# 01_detection_counter.net
KiCad netlist of a schematic drawn in Altium Designer
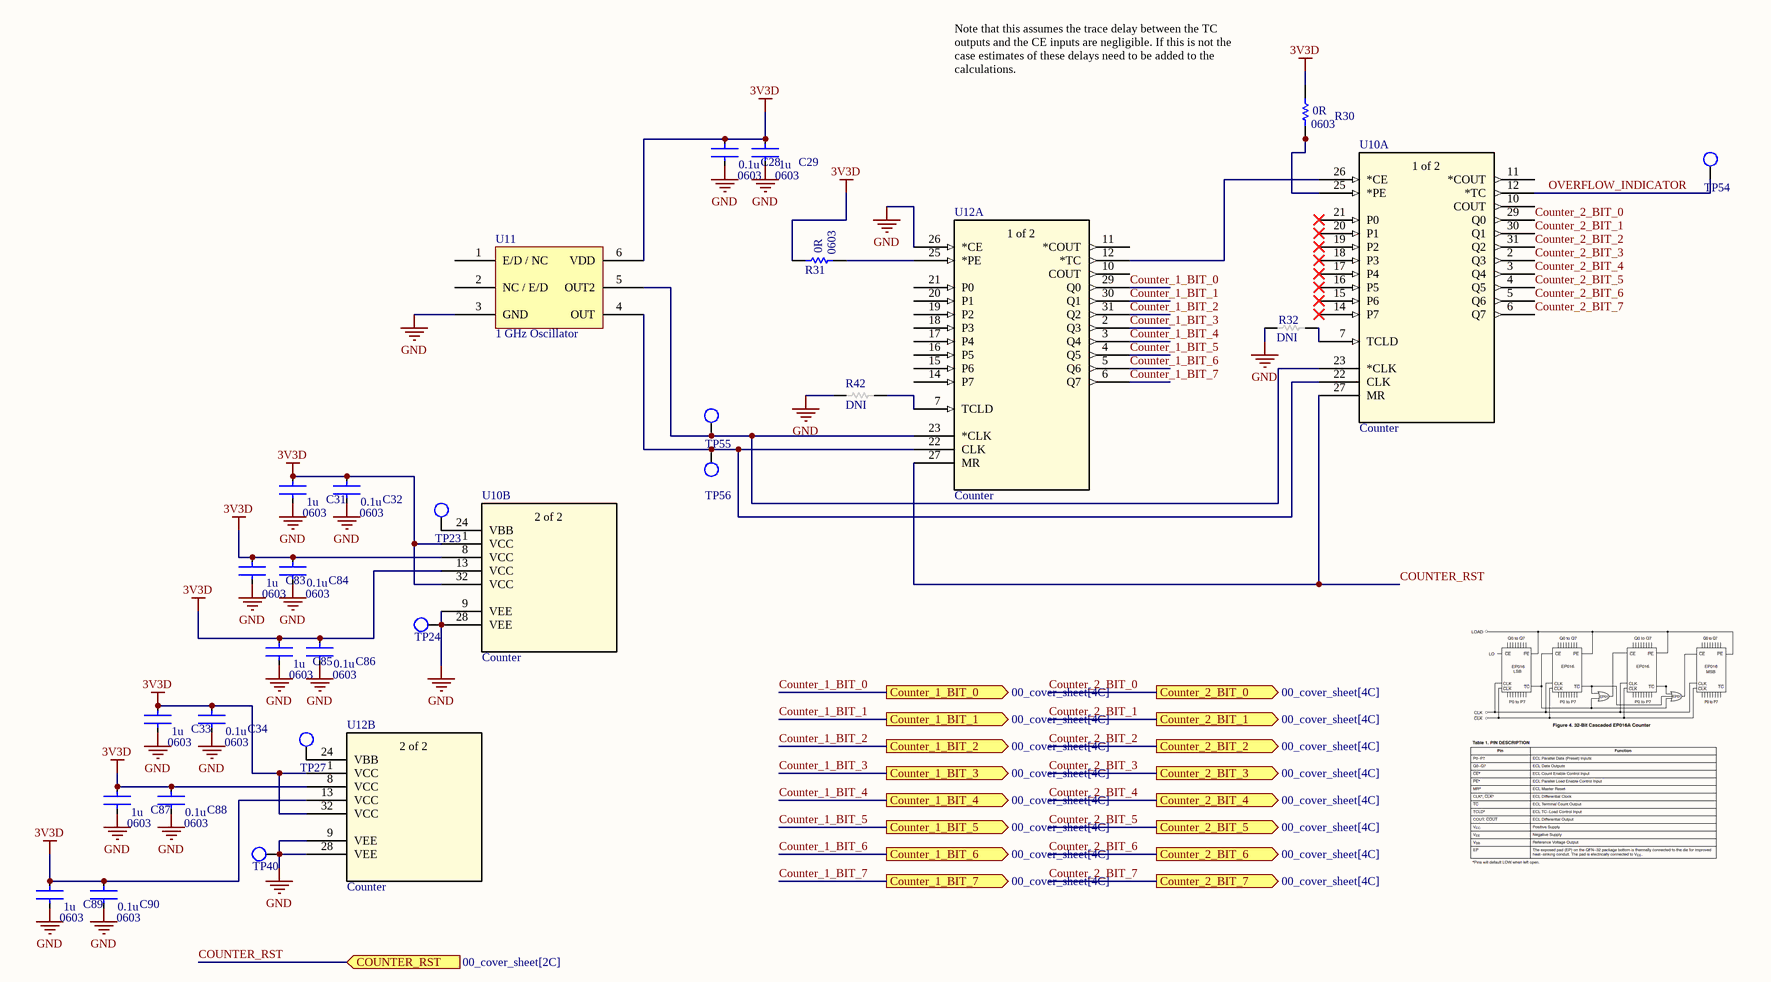
[diagram p0: 01_detection_counter.SchDoc]

(export (version "E")
  (design (tool "Eeschema 10.0.6"))
  (components
    (comp (ref "C28")
      (value "CGA3E2X7R1H104K080AA")
      (footprint "CAPTDK0603")
      (description "CAP CER 0.1UF 50V X7R 0603")
      (libsource (lib "tcspc00") (part "CGA3E2X7R1H104K080AA"))
    )
    (comp (ref "C29")
      (value "C1608X5R1E105K080AC")
      (footprint "CAPTDK0603")
      (description "CAP CER 1UF 25V X5R 0603")
      (libsource (lib "tcspc00") (part "C1608X5R1E105K080AC"))
    )
    (comp (ref "C31")
      (value "C1608X5R1E105K080AC")
      (footprint "CAPTDK0603")
      (description "CAP CER 1UF 25V X5R 0603")
      (libsource (lib "tcspc00") (part "C1608X5R1E105K080AC"))
    )
    (comp (ref "C32")
      (value "CGA3E2X7R1H104K080AA")
      (footprint "CAPTDK0603")
      (description "CAP CER 0.1UF 50V X7R 0603")
      (libsource (lib "tcspc00") (part "CGA3E2X7R1H104K080AA"))
    )
    (comp (ref "C33")
      (value "C1608X5R1E105K080AC")
      (footprint "CAPTDK0603")
      (description "CAP CER 1UF 25V X5R 0603")
      (libsource (lib "tcspc00") (part "C1608X5R1E105K080AC"))
    )
    (comp (ref "C34")
      (value "CGA3E2X7R1H104K080AA")
      (footprint "CAPTDK0603")
      (description "CAP CER 0.1UF 50V X7R 0603")
      (libsource (lib "tcspc00") (part "CGA3E2X7R1H104K080AA"))
    )
    (comp (ref "C83")
      (value "C1608X5R1E105K080AC")
      (footprint "CAPTDK0603")
      (description "CAP CER 1UF 25V X5R 0603")
      (libsource (lib "tcspc00") (part "C1608X5R1E105K080AC"))
    )
    (comp (ref "C84")
      (value "CGA3E2X7R1H104K080AA")
      (footprint "CAPTDK0603")
      (description "CAP CER 0.1UF 50V X7R 0603")
      (libsource (lib "tcspc00") (part "CGA3E2X7R1H104K080AA"))
    )
    (comp (ref "C85")
      (value "C1608X5R1E105K080AC")
      (footprint "CAPTDK0603")
      (description "CAP CER 1UF 25V X5R 0603")
      (libsource (lib "tcspc00") (part "C1608X5R1E105K080AC"))
    )
    (comp (ref "C86")
      (value "CGA3E2X7R1H104K080AA")
      (footprint "CAPTDK0603")
      (description "CAP CER 0.1UF 50V X7R 0603")
      (libsource (lib "tcspc00") (part "CGA3E2X7R1H104K080AA"))
    )
    (comp (ref "C87")
      (value "C1608X5R1E105K080AC")
      (footprint "CAPTDK0603")
      (description "CAP CER 1UF 25V X5R 0603")
      (libsource (lib "tcspc00") (part "C1608X5R1E105K080AC"))
    )
    (comp (ref "C88")
      (value "CGA3E2X7R1H104K080AA")
      (footprint "CAPTDK0603")
      (description "CAP CER 0.1UF 50V X7R 0603")
      (libsource (lib "tcspc00") (part "CGA3E2X7R1H104K080AA"))
    )
    (comp (ref "C89")
      (value "C1608X5R1E105K080AC")
      (footprint "CAPTDK0603")
      (description "CAP CER 1UF 25V X5R 0603")
      (libsource (lib "tcspc00") (part "C1608X5R1E105K080AC"))
    )
    (comp (ref "C90")
      (value "CGA3E2X7R1H104K080AA")
      (footprint "CAPTDK0603")
      (description "CAP CER 0.1UF 50V X7R 0603")
      (libsource (lib "tcspc00") (part "CGA3E2X7R1H104K080AA"))
    )
    (comp (ref "R30")
      (value "RMCF0603ZT0R00")
      (footprint "RES-STACK-POLE-0603")
      (description "RES 0 OHM JUMPER 1/10W 0603")
      (libsource (lib "tcspc00") (part "RMCF0603ZT0R00"))
    )
    (comp (ref "R31")
      (value "RMCF0603ZT0R00")
      (footprint "RES-STACK-POLE-0603")
      (description "RES 0 OHM JUMPER 1/10W 0603")
      (libsource (lib "tcspc00") (part "RMCF0603ZT0R00"))
    )
    (comp (ref "R32")
      (value "DNI")
      (footprint "RES_0603")
      (description "RES DNI 0603")
      (libsource (lib "tcspc00") (part "R0603"))
    )
    (comp (ref "R42")
      (value "DNI")
      (footprint "RES_0603")
      (description "RES DNI 0603")
      (libsource (lib "tcspc00") (part "R0603"))
    )
    (comp (ref "TP23")
      (value "TESTPOINT_S")
      (footprint "TESTPOINT_S")
      (description "Testpoint Surface Pad")
      (libsource (lib "tcspc00") (part "TESTPOINT_S"))
    )
    (comp (ref "TP24")
      (value "TESTPOINT_S")
      (footprint "TESTPOINT_S")
      (description "Testpoint Surface Pad")
      (libsource (lib "tcspc00") (part "TESTPOINT_S"))
    )
    (comp (ref "TP27")
      (value "TESTPOINT_S")
      (footprint "TESTPOINT_S")
      (description "Testpoint Surface Pad")
      (libsource (lib "tcspc00") (part "TESTPOINT_S"))
    )
    (comp (ref "TP40")
      (value "TESTPOINT_S")
      (footprint "TESTPOINT_S")
      (description "Testpoint Surface Pad")
      (libsource (lib "tcspc00") (part "TESTPOINT_S"))
    )
    (comp (ref "TP54")
      (value "TESTPOINT_S")
      (footprint "TESTPOINT_S")
      (description "Testpoint Surface Pad")
      (libsource (lib "tcspc00") (part "TESTPOINT_S"))
    )
    (comp (ref "TP55")
      (value "TESTPOINT_S")
      (footprint "TESTPOINT_S")
      (description "Testpoint Surface Pad")
      (libsource (lib "tcspc00") (part "TESTPOINT_S"))
    )
    (comp (ref "TP56")
      (value "TESTPOINT_S")
      (footprint "TESTPOINT_S")
      (description "Testpoint Surface Pad")
      (libsource (lib "tcspc00") (part "TESTPOINT_S"))
    )
    (comp (ref "U10")
      (value "Counter")
      (footprint "LQFP32_7X7_ONS")
      (description "IC BINARY COUNTER 8-BIT 32LQFP")
      (libsource (lib "tcspc00") (part "MC100EP016AFAG"))
    )
    (comp (ref "U11")
      (value "1 GHz Oscillator")
      (footprint "XLP736A00.0000001")
      (fields (field (name "MANUFACTURER") "Renesas Electronics Corporation"))
      (libsource (lib "tcspc00") (part "XLP736A00.000000I"))
    )
    (comp (ref "U12")
      (value "Counter")
      (footprint "LQFP32_7X7_ONS")
      (description "IC BINARY COUNTER 8-BIT 32LQFP")
      (libsource (lib "tcspc00") (part "MC100EP016AFAG"))
    )
  )
  (nets
    (net (code "1") (name "/COUNTER_RST") (class "Default")
      (node (ref "U10") (pin "27") (pinfunction "MR_27") (pintype "passive"))
      (node (ref "U12") (pin "27") (pinfunction "MR_27") (pintype "passive"))
    )
    (net (code "2") (name "/Counter_1_BIT_0") (class "Default")
      (node (ref "U12") (pin "29") (pinfunction "Q0_29") (pintype "output"))
    )
    (net (code "3") (name "/Counter_1_BIT_1") (class "Default")
      (node (ref "U12") (pin "30") (pinfunction "Q1_30") (pintype "output"))
    )
    (net (code "4") (name "/Counter_1_BIT_2") (class "Default")
      (node (ref "U12") (pin "31") (pinfunction "Q2_31") (pintype "output"))
    )
    (net (code "5") (name "/Counter_1_BIT_3") (class "Default")
      (node (ref "U12") (pin "2") (pinfunction "Q3_2") (pintype "output"))
    )
    (net (code "6") (name "/Counter_1_BIT_4") (class "Default")
      (node (ref "U12") (pin "3") (pinfunction "Q4_3") (pintype "output"))
    )
    (net (code "7") (name "/Counter_1_BIT_5") (class "Default")
      (node (ref "U12") (pin "4") (pinfunction "Q5_4") (pintype "output"))
    )
    (net (code "8") (name "/Counter_1_BIT_6") (class "Default")
      (node (ref "U12") (pin "5") (pinfunction "Q6_5") (pintype "output"))
    )
    (net (code "9") (name "/Counter_1_BIT_7") (class "Default")
      (node (ref "U12") (pin "6") (pinfunction "Q7_6") (pintype "output"))
    )
    (net (code "10") (name "/Counter_2_BIT_0") (class "Default")
      (node (ref "U10") (pin "29") (pinfunction "Q0_29") (pintype "output"))
    )
    (net (code "11") (name "/Counter_2_BIT_1") (class "Default")
      (node (ref "U10") (pin "30") (pinfunction "Q1_30") (pintype "output"))
    )
    (net (code "12") (name "/Counter_2_BIT_2") (class "Default")
      (node (ref "U10") (pin "31") (pinfunction "Q2_31") (pintype "output"))
    )
    (net (code "13") (name "/Counter_2_BIT_3") (class "Default")
      (node (ref "U10") (pin "2") (pinfunction "Q3_2") (pintype "output"))
    )
    (net (code "14") (name "/Counter_2_BIT_4") (class "Default")
      (node (ref "U10") (pin "3") (pinfunction "Q4_3") (pintype "output"))
    )
    (net (code "15") (name "/Counter_2_BIT_5") (class "Default")
      (node (ref "U10") (pin "4") (pinfunction "Q5_4") (pintype "output"))
    )
    (net (code "16") (name "/Counter_2_BIT_6") (class "Default")
      (node (ref "U10") (pin "5") (pinfunction "Q6_5") (pintype "output"))
    )
    (net (code "17") (name "/Counter_2_BIT_7") (class "Default")
      (node (ref "U10") (pin "6") (pinfunction "Q7_6") (pintype "output"))
    )
    (net (code "18") (name "/OVERFLOW_INDICATOR") (class "Default")
      (node (ref "TP54") (pin "1") (pinfunction "1_1") (pintype "passive"))
      (node (ref "U10") (pin "12") (pinfunction "*TC_12") (pintype "output"))
    )
    (net (code "19") (name "3V3D") (class "Default")
      (node (ref "C28") (pin "1") (pinfunction "1_1") (pintype "passive"))
      (node (ref "C29") (pin "1") (pinfunction "1_1") (pintype "passive"))
      (node (ref "C31") (pin "1") (pinfunction "1_1") (pintype "passive"))
      (node (ref "C32") (pin "1") (pinfunction "1_1") (pintype "passive"))
      (node (ref "C33") (pin "1") (pinfunction "1_1") (pintype "passive"))
      (node (ref "C34") (pin "1") (pinfunction "1_1") (pintype "passive"))
      (node (ref "C83") (pin "1") (pinfunction "1_1") (pintype "passive"))
      (node (ref "C84") (pin "1") (pinfunction "1_1") (pintype "passive"))
      (node (ref "C85") (pin "1") (pinfunction "1_1") (pintype "passive"))
      (node (ref "C86") (pin "1") (pinfunction "1_1") (pintype "passive"))
      (node (ref "C87") (pin "1") (pinfunction "1_1") (pintype "passive"))
      (node (ref "C88") (pin "1") (pinfunction "1_1") (pintype "passive"))
      (node (ref "C89") (pin "1") (pinfunction "1_1") (pintype "passive"))
      (node (ref "C90") (pin "1") (pinfunction "1_1") (pintype "passive"))
      (node (ref "R30") (pin "2") (pinfunction "2_2") (pintype "passive"))
      (node (ref "R31") (pin "2") (pinfunction "2_2") (pintype "passive"))
      (node (ref "U10") (pin "1") (pinfunction "VCC_1") (pintype "power_in"))
      (node (ref "U10") (pin "13") (pinfunction "VCC_13") (pintype "power_in"))
      (node (ref "U10") (pin "32") (pinfunction "VCC_32") (pintype "power_in"))
      (node (ref "U10") (pin "8") (pinfunction "VCC_8") (pintype "power_in"))
      (node (ref "U11") (pin "6") (pinfunction "VDD_6") (pintype "passive"))
      (node (ref "U12") (pin "1") (pinfunction "VCC_1") (pintype "power_in"))
      (node (ref "U12") (pin "13") (pinfunction "VCC_13") (pintype "power_in"))
      (node (ref "U12") (pin "32") (pinfunction "VCC_32") (pintype "power_in"))
      (node (ref "U12") (pin "8") (pinfunction "VCC_8") (pintype "power_in"))
    )
    (net (code "20") (name "GND") (class "Default")
      (node (ref "C28") (pin "2") (pinfunction "2_2") (pintype "passive"))
      (node (ref "C29") (pin "2") (pinfunction "2_2") (pintype "passive"))
      (node (ref "C31") (pin "2") (pinfunction "2_2") (pintype "passive"))
      (node (ref "C32") (pin "2") (pinfunction "2_2") (pintype "passive"))
      (node (ref "C33") (pin "2") (pinfunction "2_2") (pintype "passive"))
      (node (ref "C34") (pin "2") (pinfunction "2_2") (pintype "passive"))
      (node (ref "C83") (pin "2") (pinfunction "2_2") (pintype "passive"))
      (node (ref "C84") (pin "2") (pinfunction "2_2") (pintype "passive"))
      (node (ref "C85") (pin "2") (pinfunction "2_2") (pintype "passive"))
      (node (ref "C86") (pin "2") (pinfunction "2_2") (pintype "passive"))
      (node (ref "C87") (pin "2") (pinfunction "2_2") (pintype "passive"))
      (node (ref "C88") (pin "2") (pinfunction "2_2") (pintype "passive"))
      (node (ref "C89") (pin "2") (pinfunction "2_2") (pintype "passive"))
      (node (ref "C90") (pin "2") (pinfunction "2_2") (pintype "passive"))
      (node (ref "R32") (pin "1") (pinfunction "1_1") (pintype "passive"))
      (node (ref "R42") (pin "1") (pinfunction "1_1") (pintype "passive"))
      (node (ref "TP24") (pin "1") (pinfunction "1_1") (pintype "passive"))
      (node (ref "TP40") (pin "1") (pinfunction "1_1") (pintype "passive"))
      (node (ref "U10") (pin "28") (pinfunction "VEE_28") (pintype "power_in"))
      (node (ref "U10") (pin "9") (pinfunction "VEE_9") (pintype "power_in"))
      (node (ref "U11") (pin "3") (pinfunction "GND_3") (pintype "passive"))
      (node (ref "U12") (pin "26") (pinfunction "*CE_26") (pintype "input"))
      (node (ref "U12") (pin "28") (pinfunction "VEE_28") (pintype "power_in"))
      (node (ref "U12") (pin "9") (pinfunction "VEE_9") (pintype "power_in"))
    )
    (net (code "21") (name "Net-(U10A-*CE)") (class "Default")
      (node (ref "U10") (pin "26") (pinfunction "*CE_26") (pintype "input"))
      (node (ref "U12") (pin "12") (pinfunction "*TC_12") (pintype "output"))
    )
    (net (code "22") (name "Net-(U10A-*CLK)") (class "Default")
      (node (ref "TP55") (pin "1") (pinfunction "1_1") (pintype "passive"))
      (node (ref "U10") (pin "23") (pinfunction "*CLK_23") (pintype "passive"))
      (node (ref "U11") (pin "5") (pinfunction "OUT2_5") (pintype "passive"))
      (node (ref "U12") (pin "23") (pinfunction "*CLK_23") (pintype "passive"))
    )
    (net (code "23") (name "Net-(U10A-*PE)") (class "Default")
      (node (ref "R30") (pin "1") (pinfunction "1_1") (pintype "passive"))
      (node (ref "U10") (pin "25") (pinfunction "*PE_25") (pintype "input"))
    )
    (net (code "24") (name "Net-(U10A-CLK)") (class "Default")
      (node (ref "TP56") (pin "1") (pinfunction "1_1") (pintype "passive"))
      (node (ref "U10") (pin "22") (pinfunction "CLK_22") (pintype "passive"))
      (node (ref "U11") (pin "4") (pinfunction "OUT_4") (pintype "passive"))
      (node (ref "U12") (pin "22") (pinfunction "CLK_22") (pintype "passive"))
    )
    (net (code "25") (name "Net-(U10A-TCLD)") (class "Default")
      (node (ref "R32") (pin "2") (pinfunction "2_2") (pintype "passive"))
      (node (ref "U10") (pin "7") (pinfunction "TCLD_7") (pintype "input"))
    )
    (net (code "26") (name "Net-(U10B-VBB)") (class "Default")
      (node (ref "TP23") (pin "1") (pinfunction "1_1") (pintype "passive"))
      (node (ref "U10") (pin "24") (pinfunction "VBB_24") (pintype "power_in"))
    )
    (net (code "27") (name "Net-(U12A-*PE)") (class "Default")
      (node (ref "R31") (pin "1") (pinfunction "1_1") (pintype "passive"))
      (node (ref "U12") (pin "25") (pinfunction "*PE_25") (pintype "input"))
    )
    (net (code "28") (name "Net-(U12A-TCLD)") (class "Default")
      (node (ref "R42") (pin "2") (pinfunction "2_2") (pintype "passive"))
      (node (ref "U12") (pin "7") (pinfunction "TCLD_7") (pintype "input"))
    )
    (net (code "29") (name "Net-(U12B-VBB)") (class "Default")
      (node (ref "TP27") (pin "1") (pinfunction "1_1") (pintype "passive"))
      (node (ref "U12") (pin "24") (pinfunction "VBB_24") (pintype "power_in"))
    )
    (net (code "30") (name "unconnected-(U10A-*COUT-Pad11)") (class "Default")
      (node (ref "U10") (pin "11") (pinfunction "*COUT_11") (pintype "output"))
    )
    (net (code "31") (name "unconnected-(U10A-COUT-Pad10)") (class "Default")
      (node (ref "U10") (pin "10") (pinfunction "COUT_10") (pintype "output"))
    )
    (net (code "32") (name "unconnected-(U10A-P0-Pad21)") (class "Default")
      (node (ref "U10") (pin "21") (pinfunction "P0_21") (pintype "input+no_connect"))
    )
    (net (code "33") (name "unconnected-(U10A-P1-Pad20)") (class "Default")
      (node (ref "U10") (pin "20") (pinfunction "P1_20") (pintype "input+no_connect"))
    )
    (net (code "34") (name "unconnected-(U10A-P2-Pad19)") (class "Default")
      (node (ref "U10") (pin "19") (pinfunction "P2_19") (pintype "input+no_connect"))
    )
    (net (code "35") (name "unconnected-(U10A-P3-Pad18)") (class "Default")
      (node (ref "U10") (pin "18") (pinfunction "P3_18") (pintype "input+no_connect"))
    )
    (net (code "36") (name "unconnected-(U10A-P4-Pad17)") (class "Default")
      (node (ref "U10") (pin "17") (pinfunction "P4_17") (pintype "input+no_connect"))
    )
    (net (code "37") (name "unconnected-(U10A-P5-Pad16)") (class "Default")
      (node (ref "U10") (pin "16") (pinfunction "P5_16") (pintype "input+no_connect"))
    )
    (net (code "38") (name "unconnected-(U10A-P6-Pad15)") (class "Default")
      (node (ref "U10") (pin "15") (pinfunction "P6_15") (pintype "input+no_connect"))
    )
    (net (code "39") (name "unconnected-(U10A-P7-Pad14)") (class "Default")
      (node (ref "U10") (pin "14") (pinfunction "P7_14") (pintype "input+no_connect"))
    )
    (net (code "40") (name "unconnected-(U11-E{slash}D_{slash}_NC-Pad1)") (class "Default")
      (node (ref "U11") (pin "1") (pinfunction "E/D_/_NC_1") (pintype "passive"))
    )
    (net (code "41") (name "unconnected-(U11-NC_{slash}_E{slash}D-Pad2)") (class "Default")
      (node (ref "U11") (pin "2") (pinfunction "NC_/_E/D_2") (pintype "passive"))
    )
    (net (code "42") (name "unconnected-(U12A-*COUT-Pad11)") (class "Default")
      (node (ref "U12") (pin "11") (pinfunction "*COUT_11") (pintype "output"))
    )
    (net (code "43") (name "unconnected-(U12A-COUT-Pad10)") (class "Default")
      (node (ref "U12") (pin "10") (pinfunction "COUT_10") (pintype "output"))
    )
    (net (code "44") (name "unconnected-(U12A-P0-Pad21)") (class "Default")
      (node (ref "U12") (pin "21") (pinfunction "P0_21") (pintype "input"))
    )
    (net (code "45") (name "unconnected-(U12A-P1-Pad20)") (class "Default")
      (node (ref "U12") (pin "20") (pinfunction "P1_20") (pintype "input"))
    )
    (net (code "46") (name "unconnected-(U12A-P2-Pad19)") (class "Default")
      (node (ref "U12") (pin "19") (pinfunction "P2_19") (pintype "input"))
    )
    (net (code "47") (name "unconnected-(U12A-P3-Pad18)") (class "Default")
      (node (ref "U12") (pin "18") (pinfunction "P3_18") (pintype "input"))
    )
    (net (code "48") (name "unconnected-(U12A-P4-Pad17)") (class "Default")
      (node (ref "U12") (pin "17") (pinfunction "P4_17") (pintype "input"))
    )
    (net (code "49") (name "unconnected-(U12A-P5-Pad16)") (class "Default")
      (node (ref "U12") (pin "16") (pinfunction "P5_16") (pintype "input"))
    )
    (net (code "50") (name "unconnected-(U12A-P6-Pad15)") (class "Default")
      (node (ref "U12") (pin "15") (pinfunction "P6_15") (pintype "input"))
    )
    (net (code "51") (name "unconnected-(U12A-P7-Pad14)") (class "Default")
      (node (ref "U12") (pin "14") (pinfunction "P7_14") (pintype "input"))
    )
  )
)
